# can_unisolated.net
KiCad netlist of a schematic drawn in Altium Designer
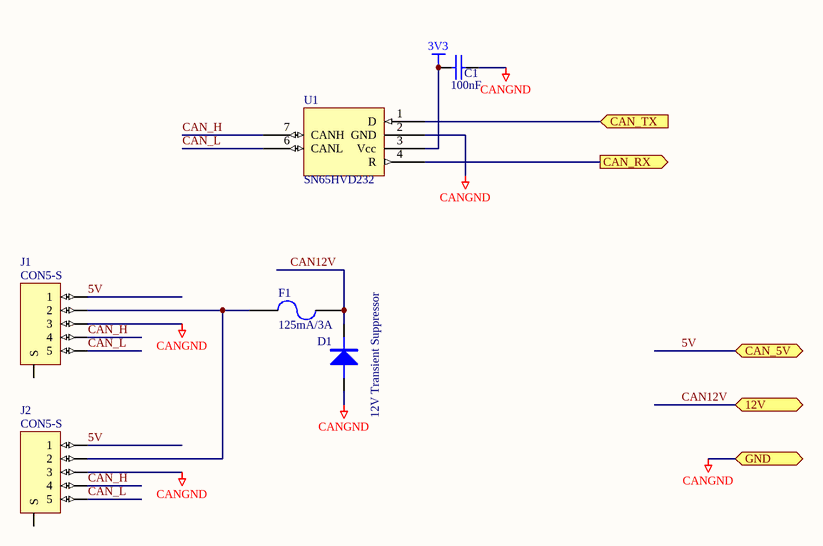
[diagram p0: can_unisolated.SchDoc]

(export (version "E")
  (design (tool "Eeschema 10.0.6"))
  (components
    (comp (ref "C1")
      (value "100nF")
      (footprint "0603")
      (description "Capacitor")
      (libsource (lib "*") (part "CAP"))
    )
    (comp (ref "D1")
      (value "12V Transient Suppressor")
      (footprint "SMA")
      (description "Diode")
      (libsource (lib "RCLDQ") (part "DIODE"))
    )
    (comp (ref "F1")
      (value "125mA/3A")
      (footprint "LITTELFUSE-154")
      (description "Fuse")
      (libsource (lib "*") (part "FUSE2"))
    )
    (comp (ref "J1")
      (value "CON5-S")
      (footprint "TRIAD5F")
      (description "Connector, 2 pin, with shield @ S")
      (libsource (lib "*") (part "CON5-S"))
    )
    (comp (ref "J2")
      (value "CON5-S")
      (footprint "TRIAD5F")
      (description "Connector, 2 pin, with shield @ S")
      (libsource (lib "*") (part "CON5-S"))
    )
    (comp (ref "U1")
      (value "SN65HVD232")
      (footprint "SO8")
      (description "3.3V CAN Transciever")
      (libsource (lib "*") (part "SN65HVD232"))
    )
  )
  (nets
    (net (code "1") (name "/5V") (class "Default")
      (node (ref "J1") (pin "1") (pinfunction "1_1") (pintype "bidirectional"))
      (node (ref "J2") (pin "1") (pinfunction "1_1") (pintype "bidirectional"))
    )
    (net (code "2") (name "/CAN12V") (class "Default")
      (node (ref "D1") (pin "K") (pinfunction "K_K") (pintype "passive"))
      (node (ref "F1") (pin "2") (pinfunction "2_2") (pintype "passive"))
    )
    (net (code "3") (name "/CAN_H") (class "Default")
      (node (ref "J1") (pin "4") (pinfunction "4_4") (pintype "bidirectional"))
      (node (ref "J2") (pin "4") (pinfunction "4_4") (pintype "bidirectional"))
      (node (ref "U1") (pin "7") (pinfunction "CANH_7") (pintype "bidirectional"))
    )
    (net (code "4") (name "/CAN_L") (class "Default")
      (node (ref "J1") (pin "5") (pinfunction "5_5") (pintype "bidirectional"))
      (node (ref "J2") (pin "5") (pinfunction "5_5") (pintype "bidirectional"))
      (node (ref "U1") (pin "6") (pinfunction "CANL_6") (pintype "bidirectional"))
    )
    (net (code "5") (name "/CAN_RX") (class "Default")
      (node (ref "U1") (pin "4") (pinfunction "R_4") (pintype "output"))
    )
    (net (code "6") (name "/CAN_TX") (class "Default")
      (node (ref "U1") (pin "1") (pinfunction "D_1") (pintype "input"))
    )
    (net (code "7") (name "3V3") (class "Default")
      (node (ref "C1") (pin "2") (pinfunction "2_2") (pintype "passive"))
      (node (ref "U1") (pin "3") (pinfunction "Vcc_3") (pintype "power_in"))
    )
    (net (code "8") (name "CANGND") (class "Default")
      (node (ref "C1") (pin "1") (pinfunction "1_1") (pintype "passive"))
      (node (ref "D1") (pin "A") (pinfunction "A_A") (pintype "passive"))
      (node (ref "J1") (pin "3") (pinfunction "3_3") (pintype "bidirectional"))
      (node (ref "J2") (pin "3") (pinfunction "3_3") (pintype "bidirectional"))
      (node (ref "U1") (pin "2") (pinfunction "GND_2") (pintype "power_in"))
    )
    (net (code "9") (name "Net-(F1-Pad1)") (class "Default")
      (node (ref "F1") (pin "1") (pinfunction "1_1") (pintype "passive"))
      (node (ref "J1") (pin "2") (pinfunction "2_2") (pintype "bidirectional"))
      (node (ref "J2") (pin "2") (pinfunction "2_2") (pintype "bidirectional"))
    )
    (net (code "10") (name "unconnected-(J1-S-Pad0)") (class "Default")
      (node (ref "J1") (pin "0") (pinfunction "S_0") (pintype "bidirectional"))
    )
    (net (code "11") (name "unconnected-(J2-S-Pad0)") (class "Default")
      (node (ref "J2") (pin "0") (pinfunction "S_0") (pintype "bidirectional"))
    )
  )
)
